# psu.net
KiCad netlist of a schematic drawn in Altium Designer
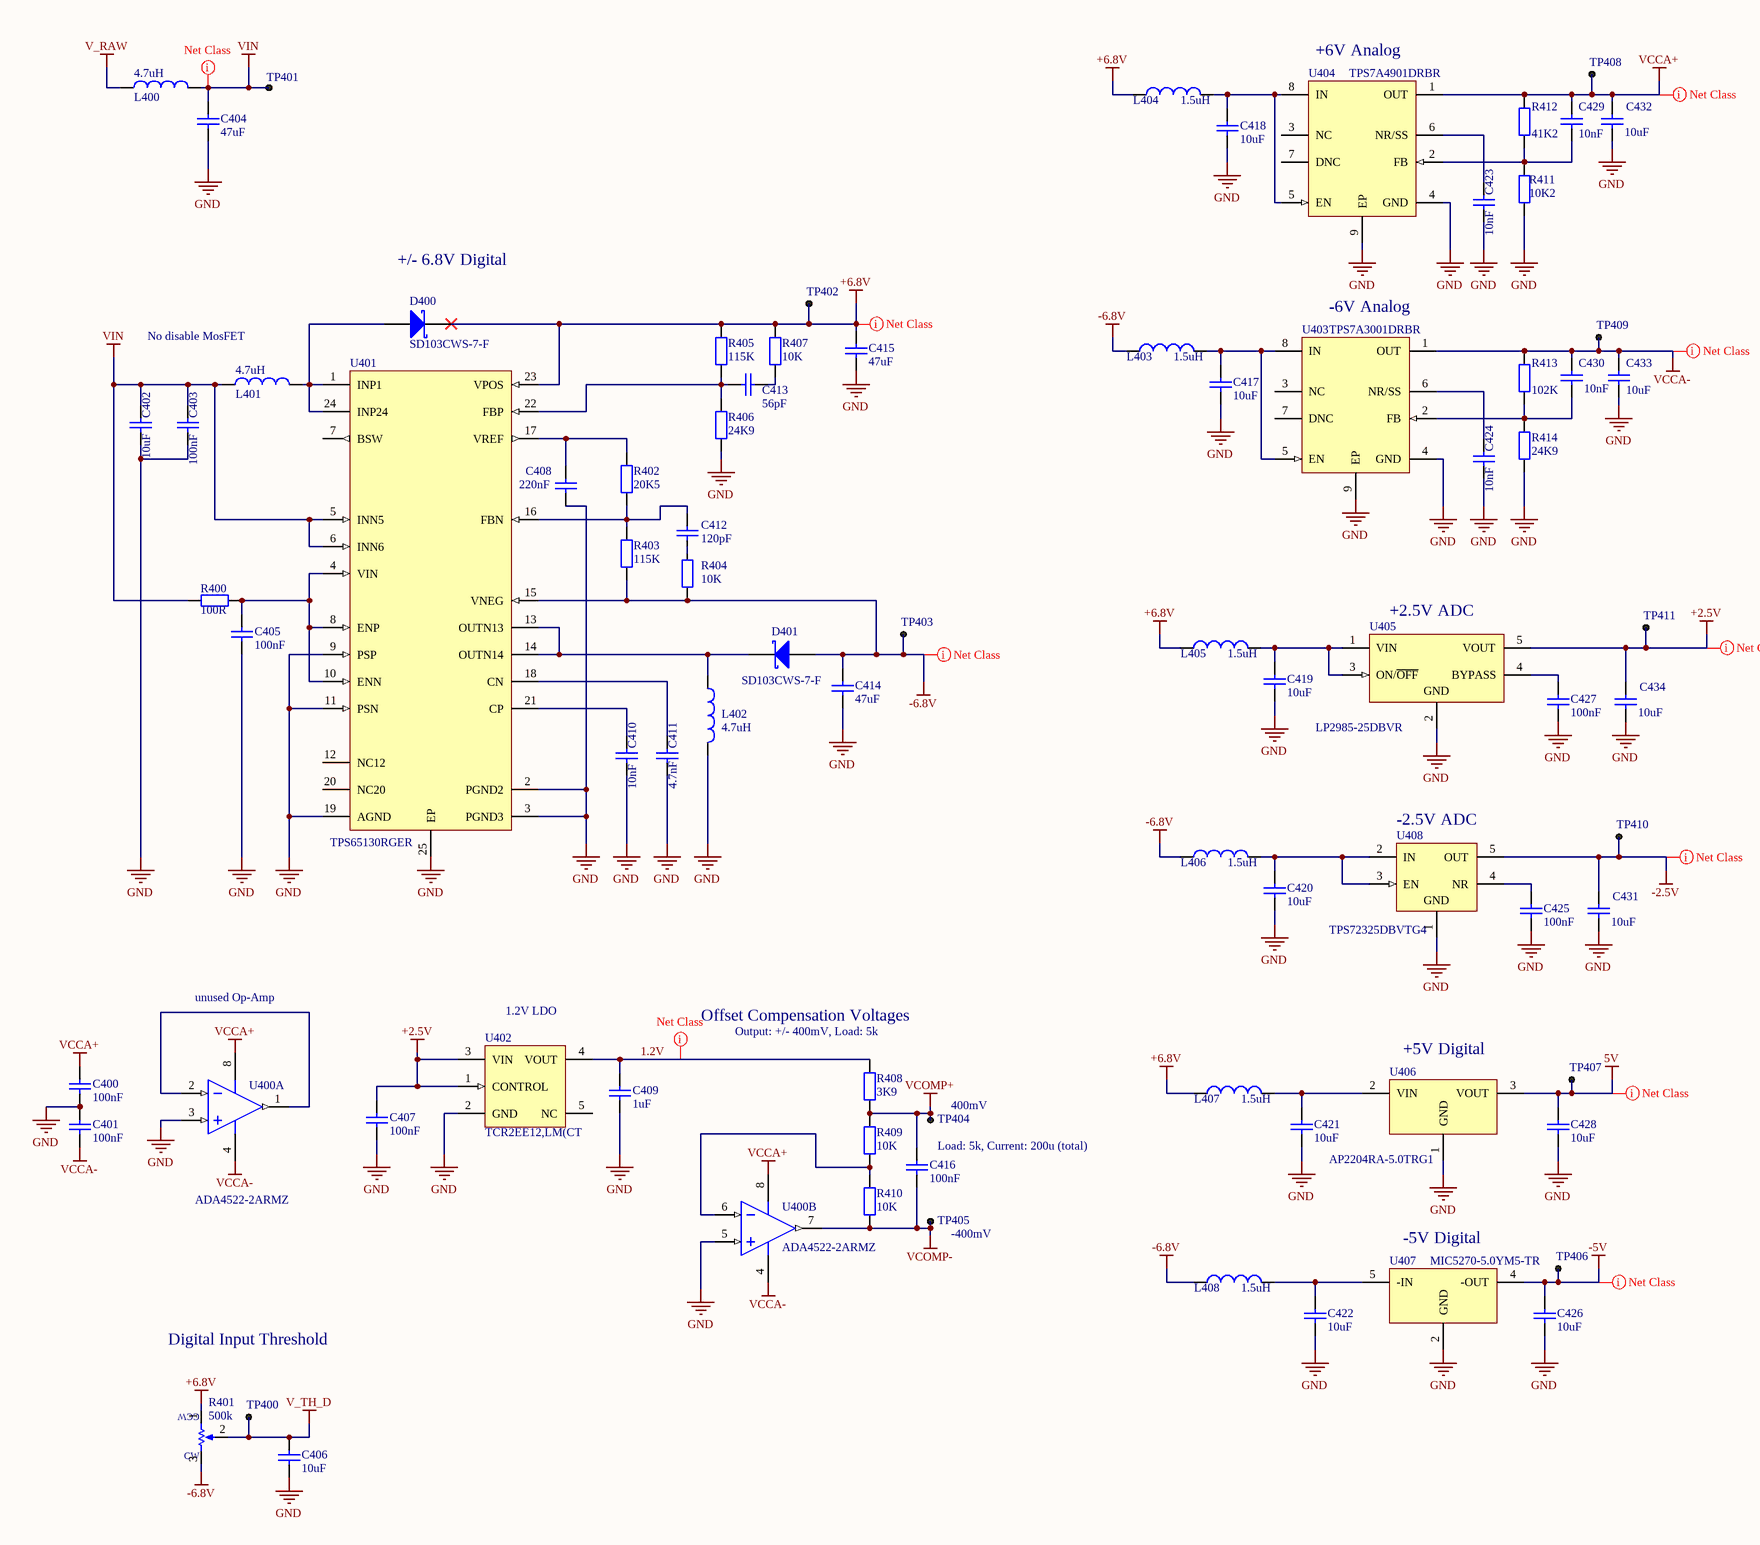
[diagram p0: psu.SchDoc]

(export (version "E")
  (design (tool "Eeschema 10.0.6"))
  (components
    (comp (ref "C400")
      (value "100nF")
      (footprint "CAPC0402(1005)60_L")
      (description "CAP 100nF 16V -20% to +80% 0402 (1005 Metric) Thickness 0.6mm SMD")
      (fields (field (name "TOLERANCE") "-20% to +80%"))
      (libsource (lib "Altium Content Vault") (part "CMP-1034-02071-1"))
    )
    (comp (ref "C401")
      (value "100nF")
      (footprint "CAPC0402(1005)60_L")
      (description "CAP 100nF 16V -20% to +80% 0402 (1005 Metric) Thickness 0.6mm SMD")
      (fields (field (name "TOLERANCE") "-20% to +80%"))
      (libsource (lib "Altium Content Vault") (part "CMP-1034-02071-1"))
    )
    (comp (ref "C402")
      (value "10uF")
      (footprint "CAPC0603(1608)100_L")
      (description "CAP 10uF 10V ±20% 0603 (1608 Metric) Thickness 1mm SMD")
      (fields (field (name "TOLERANCE") "Â±20%"))
      (libsource (lib "Altium Content Vault") (part "CMP-1035-02800-1"))
    )
    (comp (ref "C403")
      (value "100nF")
      (footprint "CAPC0402(1005)60_L")
      (description "CAP 100nF 16V -20% to +80% 0402 (1005 Metric) Thickness 0.6mm SMD")
      (fields (field (name "TOLERANCE") "-20% to +80%"))
      (libsource (lib "Altium Content Vault") (part "CMP-1034-02071-1"))
    )
    (comp (ref "C404")
      (value "47uF")
      (footprint "CAPC1210(3225)280_L")
      (description "CAP 47uF 16V ±20% 1210 (3225 Metric) Thickness 2.8mm SMD")
      (fields (field (name "TOLERANCE") "Â±20%"))
      (libsource (lib "Altium Content Vault") (part "CMP-1038-02296-1"))
    )
    (comp (ref "C405")
      (value "100nF")
      (footprint "CAPC0402(1005)60_L")
      (description "CAP 100nF 16V -20% to +80% 0402 (1005 Metric) Thickness 0.6mm SMD")
      (fields (field (name "TOLERANCE") "-20% to +80%"))
      (libsource (lib "Altium Content Vault") (part "CMP-1034-02071-1"))
    )
    (comp (ref "C406")
      (value "10uF")
      (footprint "CAPC0603(1608)100_L")
      (description "CAP 10uF 10V ±20% 0603 (1608 Metric) Thickness 1mm SMD")
      (fields (field (name "TOLERANCE") "Â±20%"))
      (libsource (lib "Altium Content Vault") (part "CMP-1035-02800-1"))
    )
    (comp (ref "C407")
      (value "100nF")
      (footprint "CAPC0402(1005)60_L")
      (description "CAP 100nF 16V -20% to +80% 0402 (1005 Metric) Thickness 0.6mm SMD")
      (fields (field (name "TOLERANCE") "-20% to +80%"))
      (libsource (lib "Altium Content Vault") (part "CMP-1034-02071-1"))
    )
    (comp (ref "C408")
      (value "220nF")
      (footprint "CAPC0402(1005)60_L")
      (description "CAP 220nF 10V -20% to +80% 0402 (1005 Metric) Thickness 0.6mm SMD")
      (fields (field (name "TOLERANCE") "-20% to +80%"))
      (libsource (lib "Altium Content Vault") (part "CMP-1034-02088-1"))
    )
    (comp (ref "C409")
      (value "1uF")
      (footprint "CAPC0402(1005)60_L")
      (description "CAP 1uF 16V ±20% 0402 (1005 Metric) Thickness 0.6mm SMD")
      (fields (field (name "TOLERANCE") "Â±20%"))
      (libsource (lib "Altium Content Vault") (part "CAP"))
    )
    (comp (ref "C410")
      (value "10nF")
      (footprint "CAPC0402(1005)60_L")
      (description "CAP 10nF 25V ±5% 0402 (1005 Metric) Thickness 0.6mm SMDC")
      (fields (field (name "TOLERANCE") "Â±5%"))
      (libsource (lib "Altium Content Vault") (part "CAP"))
    )
    (comp (ref "C411")
      (value "4.7nF")
      (footprint "CAPC0402(1005)60_L")
      (description "CAP 4.7nF 100V ±10% 0402 (1005 Metric) Thickness 0.6mm SMD")
      (fields (field (name "TOLERANCE") "Â±10%"))
      (libsource (lib "Altium Content Vault") (part "CMP-1034-01819-1"))
    )
    (comp (ref "C412")
      (value "120pF")
      (footprint "CAPC0402(1005)60_L")
      (description "CAP 120pF 100V ±1% 0402 (1005 Metric) Thickness 0.6mm SMD")
      (fields (field (name "TOLERANCE") "Â±1%"))
      (libsource (lib "Altium Content Vault") (part "CMP-1034-01278-1"))
    )
    (comp (ref "C413")
      (value "56pF")
      (footprint "CAPC0402(1005)60_L")
      (description "CAP 56pF 100V ±1% 0402 (1005 Metric) Thickness 0.6mm SMD")
      (fields (field (name "TOLERANCE") "Â±1%"))
      (libsource (lib "Altium Content Vault") (part "CMP-1034-01134-1"))
    )
    (comp (ref "C414")
      (value "47uF")
      (footprint "CAPC1210(3225)280_L")
      (description "CAP 47uF 16V ±20% 1210 (3225 Metric) Thickness 2.8mm SMD")
      (fields (field (name "TOLERANCE") "Â±20%"))
      (libsource (lib "Altium Content Vault") (part "CMP-1038-02296-1"))
    )
    (comp (ref "C415")
      (value "47uF")
      (footprint "CAPC1210(3225)280_L")
      (description "CAP 47uF 16V ±20% 1210 (3225 Metric) Thickness 2.8mm SMD")
      (fields (field (name "TOLERANCE") "Â±20%"))
      (libsource (lib "Altium Content Vault") (part "CMP-1038-02296-1"))
    )
    (comp (ref "C416")
      (value "100nF")
      (footprint "CAPC0402(1005)60_L")
      (description "CAP 100nF 16V -20% to +80% 0402 (1005 Metric) Thickness 0.6mm SMD")
      (fields (field (name "TOLERANCE") "-20% to +80%"))
      (libsource (lib "Altium Content Vault") (part "CMP-1034-02071-1"))
    )
    (comp (ref "C417")
      (value "10uF")
      (footprint "CAPC0603(1608)100_L")
      (description "CAP 10uF 10V ±20% 0603 (1608 Metric) Thickness 1mm SMD")
      (fields (field (name "TOLERANCE") "Â±20%"))
      (libsource (lib "Altium Content Vault") (part "CMP-1035-02800-1"))
    )
    (comp (ref "C418")
      (value "10uF")
      (footprint "CAPC0603(1608)100_L")
      (description "CAP 10uF 10V ±20% 0603 (1608 Metric) Thickness 1mm SMD")
      (fields (field (name "TOLERANCE") "Â±20%"))
      (libsource (lib "Altium Content Vault") (part "CMP-1035-02800-1"))
    )
    (comp (ref "C419")
      (value "10uF")
      (footprint "CAPC0603(1608)100_L")
      (description "CAP 10uF 10V ±20% 0603 (1608 Metric) Thickness 1mm SMD")
      (fields (field (name "TOLERANCE") "Â±20%"))
      (libsource (lib "Altium Content Vault") (part "CMP-1035-02800-1"))
    )
    (comp (ref "C420")
      (value "10uF")
      (footprint "CAPC0603(1608)100_L")
      (description "CAP 10uF 10V ±20% 0603 (1608 Metric) Thickness 1mm SMD")
      (fields (field (name "TOLERANCE") "Â±20%"))
      (libsource (lib "Altium Content Vault") (part "CMP-1035-02800-1"))
    )
    (comp (ref "C421")
      (value "10uF")
      (footprint "CAPC0603(1608)100_L")
      (description "CAP 10uF 10V ±20% 0603 (1608 Metric) Thickness 1mm SMD")
      (fields (field (name "TOLERANCE") "Â±20%"))
      (libsource (lib "Altium Content Vault") (part "CMP-1035-02800-1"))
    )
    (comp (ref "C422")
      (value "10uF")
      (footprint "CAPC0603(1608)100_L")
      (description "CAP 10uF 10V ±20% 0603 (1608 Metric) Thickness 1mm SMD")
      (fields (field (name "TOLERANCE") "Â±20%"))
      (libsource (lib "Altium Content Vault") (part "CMP-1035-02800-1"))
    )
    (comp (ref "C423")
      (value "10nF")
      (footprint "CAPC0402(1005)60_L")
      (description "CAP 10nF 25V ±5% 0402 (1005 Metric) Thickness 0.6mm SMDC")
      (fields (field (name "TOLERANCE") "Â±5%"))
      (libsource (lib "Altium Content Vault") (part "CAP"))
    )
    (comp (ref "C424")
      (value "10nF")
      (footprint "CAPC0402(1005)60_L")
      (description "CAP 10nF 25V ±5% 0402 (1005 Metric) Thickness 0.6mm SMDC")
      (fields (field (name "TOLERANCE") "Â±5%"))
      (libsource (lib "Altium Content Vault") (part "CAP"))
    )
    (comp (ref "C425")
      (value "100nF")
      (footprint "CAPC0402(1005)60_L")
      (description "CAP 100nF 16V -20% to +80% 0402 (1005 Metric) Thickness 0.6mm SMD")
      (fields (field (name "TOLERANCE") "-20% to +80%"))
      (libsource (lib "Altium Content Vault") (part "CMP-1034-02071-1"))
    )
    (comp (ref "C426")
      (value "10uF")
      (footprint "CAPC0603(1608)100_L")
      (description "CAP 10uF 10V ±20% 0603 (1608 Metric) Thickness 1mm SMD")
      (fields (field (name "TOLERANCE") "Â±20%"))
      (libsource (lib "Altium Content Vault") (part "CMP-1035-02800-1"))
    )
    (comp (ref "C427")
      (value "100nF")
      (footprint "CAPC0402(1005)60_L")
      (description "CAP 100nF 16V -20% to +80% 0402 (1005 Metric) Thickness 0.6mm SMD")
      (fields (field (name "TOLERANCE") "-20% to +80%"))
      (libsource (lib "Altium Content Vault") (part "CMP-1034-02071-1"))
    )
    (comp (ref "C428")
      (value "10uF")
      (footprint "CAPC0603(1608)100_L")
      (description "CAP 10uF 10V ±20% 0603 (1608 Metric) Thickness 1mm SMD")
      (fields (field (name "TOLERANCE") "Â±20%"))
      (libsource (lib "Altium Content Vault") (part "CMP-1035-02800-1"))
    )
    (comp (ref "C429")
      (value "10nF")
      (footprint "CAPC0402(1005)60_L")
      (description "CAP 10nF 25V ±5% 0402 (1005 Metric) Thickness 0.6mm SMDC")
      (fields (field (name "TOLERANCE") "Â±5%"))
      (libsource (lib "Altium Content Vault") (part "CAP"))
    )
    (comp (ref "C430")
      (value "10nF")
      (footprint "CAPC0402(1005)60_L")
      (description "CAP 10nF 25V ±5% 0402 (1005 Metric) Thickness 0.6mm SMDC")
      (fields (field (name "TOLERANCE") "Â±5%"))
      (libsource (lib "Altium Content Vault") (part "CAP"))
    )
    (comp (ref "C431")
      (value "10uF")
      (footprint "CAPC0603(1608)100_L")
      (description "CAP 10uF 10V ±20% 0603 (1608 Metric) Thickness 1mm SMD")
      (fields (field (name "TOLERANCE") "Â±20%"))
      (libsource (lib "Altium Content Vault") (part "CMP-1035-02800-1"))
    )
    (comp (ref "C432")
      (value "10uF")
      (footprint "CAPC0603(1608)100_L")
      (description "CAP 10uF 10V ±20% 0603 (1608 Metric) Thickness 1mm SMD")
      (fields (field (name "TOLERANCE") "Â±20%"))
      (libsource (lib "Altium Content Vault") (part "CMP-1035-02800-1"))
    )
    (comp (ref "C433")
      (value "10uF")
      (footprint "CAPC0603(1608)100_L")
      (description "CAP 10uF 10V ±20% 0603 (1608 Metric) Thickness 1mm SMD")
      (fields (field (name "TOLERANCE") "Â±20%"))
      (libsource (lib "Altium Content Vault") (part "CMP-1035-02800-1"))
    )
    (comp (ref "C434")
      (value "10uF")
      (footprint "CAPC0603(1608)100_L")
      (description "CAP 10uF 10V ±20% 0603 (1608 Metric) Thickness 1mm SMD")
      (fields (field (name "TOLERANCE") "Â±20%"))
      (libsource (lib "Altium Content Vault") (part "CMP-1035-02800-1"))
    )
    (comp (ref "D400")
      (value "SD103CWS-7-F")
      (footprint "DIOD-SOD323-2_V")
      (description "DIODE SCHOTTKY 20V 350MA SOD323")
      (fields (field (name "MANUFACTURER") "Diodes Incorporated"))
      (libsource (lib "ETHZ Vault") (part "Diode Schottky"))
    )
    (comp (ref "D401")
      (value "SD103CWS-7-F")
      (footprint "DIOD-SOD323-2_V")
      (description "DIODE SCHOTTKY 20V 350MA SOD323")
      (fields (field (name "MANUFACTURER") "Diodes Incorporated"))
      (libsource (lib "ETHZ Vault") (part "Diode Schottky"))
    )
    (comp (ref "L400")
      (value "4.7uH")
      (footprint "INDC2520X10L")
      (description "FIXED IND 4.7UH 1A 110 MOHM SMD")
      (fields (field (name "TOLERANCE") "±20%") (field (name "MANUFACTURER") "TDK Corporation"))
      (libsource (lib "ETHZ Vault") (part "CMP-00119-1"))
    )
    (comp (ref "L401")
      (value "4.7uH")
      (footprint "INDC2520X10L")
      (description "FIXED IND 4.7UH 1A 110 MOHM SMD")
      (fields (field (name "TOLERANCE") "±20%") (field (name "MANUFACTURER") "TDK Corporation"))
      (libsource (lib "ETHZ Vault") (part "CMP-00119-1"))
    )
    (comp (ref "L402")
      (value "4.7uH")
      (footprint "INDC2520X10L")
      (description "FIXED IND 4.7UH 1A 110 MOHM SMD")
      (fields (field (name "TOLERANCE") "±20%") (field (name "MANUFACTURER") "TDK Corporation"))
      (libsource (lib "ETHZ Vault") (part "CMP-00119-1"))
    )
    (comp (ref "L403")
      (value "1.5uH")
      (footprint "INDC0603(1608)_L")
      (description "FIXED IND 1.5UH 50MA 700 MOHM")
      (fields (field (name "TOLERANCE") "±20%") (field (name "MANUFACTURER") "TDK Corporation"))
      (libsource (lib "ETHZ Vault") (part "CMP-00229-1"))
    )
    (comp (ref "L404")
      (value "1.5uH")
      (footprint "INDC0603(1608)_L")
      (description "FIXED IND 1.5UH 50MA 700 MOHM")
      (fields (field (name "TOLERANCE") "±20%") (field (name "MANUFACTURER") "TDK Corporation"))
      (libsource (lib "ETHZ Vault") (part "CMP-00229-1"))
    )
    (comp (ref "L405")
      (value "1.5uH")
      (footprint "INDC0603(1608)_L")
      (description "FIXED IND 1.5UH 50MA 700 MOHM")
      (fields (field (name "TOLERANCE") "±20%") (field (name "MANUFACTURER") "TDK Corporation"))
      (libsource (lib "ETHZ Vault") (part "CMP-00229-1"))
    )
    (comp (ref "L406")
      (value "1.5uH")
      (footprint "INDC0603(1608)_L")
      (description "FIXED IND 1.5UH 50MA 700 MOHM")
      (fields (field (name "TOLERANCE") "±20%") (field (name "MANUFACTURER") "TDK Corporation"))
      (libsource (lib "ETHZ Vault") (part "CMP-00229-1"))
    )
    (comp (ref "L407")
      (value "1.5uH")
      (footprint "INDC0603(1608)_L")
      (description "FIXED IND 1.5UH 50MA 700 MOHM")
      (fields (field (name "TOLERANCE") "±20%") (field (name "MANUFACTURER") "TDK Corporation"))
      (libsource (lib "ETHZ Vault") (part "CMP-00229-1"))
    )
    (comp (ref "L408")
      (value "1.5uH")
      (footprint "INDC0603(1608)_L")
      (description "FIXED IND 1.5UH 50MA 700 MOHM")
      (fields (field (name "TOLERANCE") "±20%") (field (name "MANUFACTURER") "TDK Corporation"))
      (libsource (lib "ETHZ Vault") (part "CMP-00229-1"))
    )
    (comp (ref "R400")
      (value "100R")
      (footprint "RESC0402(1005)_L")
      (description "100R 0.063W 1% 0402 (1005 Metric)  SMD")
      (fields (field (name "TOLERANCE") "1 %") (field (name "POWER") "0.063 W"))
      (libsource (lib "Altium Content Vault") (part "CMP-1011-00397-1"))
    )
    (comp (ref "R401")
      (value "500k")
      (footprint "43W")
      (description "TRIMMER 500K OHM 0.125W SMD")
      (fields (field (name "TOLERANCE") "±20%") (field (name "MANUFACTURER") "TT Electronics/BI"))
      (libsource (lib "ETHZ Vault") (part "Trimmer"))
    )
    (comp (ref "R402")
      (value "20K5")
      (footprint "RESC0402(1005)_L")
      (description "20K5 0.063W 1% 0402 (1005 Metric)  SMD")
      (fields (field (name "POWER") "0.063 W") (field (name "TOLERANCE") "1 %"))
      (libsource (lib "Altium Content Vault") (part "RES"))
    )
    (comp (ref "R403")
      (value "115K")
      (footprint "RESC0402(1005)_L")
      (description "115K 0.063W 1% 0402 (1005 Metric)  SMD")
      (fields (field (name "TOLERANCE") "1 %") (field (name "POWER") "0.063 W"))
      (libsource (lib "") (part "RES_1"))
    )
    (comp (ref "R404")
      (value "10K")
      (footprint "RESC0402(1005)_L")
      (description "10K 0.063W 1% 0402 (1005 Metric)  SMD")
      (fields (field (name "TOLERANCE") "1 %") (field (name "POWER") "0.063 W"))
      (libsource (lib "Altium Content Vault") (part "CMP-1011-00623-1"))
    )
    (comp (ref "R405")
      (value "115K")
      (footprint "RESC0402(1005)_L")
      (description "115K 0.063W 1% 0402 (1005 Metric)  SMD")
      (fields (field (name "TOLERANCE") "1 %") (field (name "POWER") "0.063 W"))
      (libsource (lib "Altium Content Vault") (part "RES"))
    )
    (comp (ref "R406")
      (value "24K9")
      (footprint "RESC0402(1005)_L")
      (description "24K9 0.063W 1% 0402 (1005 Metric)  SMD")
      (fields (field (name "TOLERANCE") "1 %") (field (name "POWER") "0.063 W"))
      (libsource (lib "Altium Content Vault") (part "RES"))
    )
    (comp (ref "R407")
      (value "10K")
      (footprint "RESC0402(1005)_L")
      (description "10K 0.063W 1% 0402 (1005 Metric)  SMD")
      (fields (field (name "TOLERANCE") "1 %") (field (name "POWER") "0.063 W"))
      (libsource (lib "Altium Content Vault") (part "CMP-1011-00623-1"))
    )
    (comp (ref "R408")
      (value "3K9")
      (footprint "RESC0402(1005)_L")
      (description "3K9 0.063W 1% 0402 (1005 Metric)  SMD")
      (fields (field (name "TOLERANCE") "1 %") (field (name "POWER") "0.063 W"))
      (libsource (lib "Altium Content Vault") (part "RES"))
    )
    (comp (ref "R409")
      (value "10K")
      (footprint "RESC0402(1005)_L")
      (description "10K 0.063W 1% 0402 (1005 Metric)  SMD")
      (fields (field (name "TOLERANCE") "1 %") (field (name "POWER") "0.063 W"))
      (libsource (lib "Altium Content Vault") (part "RES"))
    )
    (comp (ref "R410")
      (value "10K")
      (footprint "RESC0402(1005)_L")
      (description "10K 0.063W 1% 0402 (1005 Metric)  SMD")
      (fields (field (name "TOLERANCE") "1 %") (field (name "POWER") "0.063 W"))
      (libsource (lib "Altium Content Vault") (part "RES"))
    )
    (comp (ref "R411")
      (value "10K2")
      (footprint "RESC0402(1005)_L")
      (description "10K2 0.063W 1% 0402 (1005 Metric)  SMD")
      (fields (field (name "POWER") "0.063 W") (field (name "TOLERANCE") "1 %"))
      (libsource (lib "Altium Content Vault") (part "CMP-1011-00624-1"))
    )
    (comp (ref "R412")
      (value "41K2")
      (footprint "RESC0402(1005)_L")
      (description "41K2 0.063W 1% 0402 (1005 Metric)  SMD")
      (fields (field (name "TOLERANCE") "1 %") (field (name "POWER") "0.063 W"))
      (libsource (lib "Altium Content Vault") (part "CMP-1011-00692-1"))
    )
    (comp (ref "R413")
      (value "102K")
      (footprint "RESC0402(1005)_L")
      (description "102K 0.063W 1% 0402 (1005 Metric)  SMD")
      (fields (field (name "TOLERANCE") "1 %") (field (name "POWER") "0.063 W"))
      (libsource (lib "Altium Content Vault") (part "CMP-1011-00737-1"))
    )
    (comp (ref "R414")
      (value "24K9")
      (footprint "RESC0402(1005)_L")
      (description "24K9 0.063W 1% 0402 (1005 Metric)  SMD")
      (fields (field (name "TOLERANCE") "1 %") (field (name "POWER") "0.063 W"))
      (libsource (lib "Altium Content Vault") (part "CMP-1011-00666-1"))
    )
    (comp (ref "TP400")
      (value "~")
      (footprint "Pad-0.6mm")
      (description "0.6mm SMT Test Pad")
      (libsource (lib "ETHZ Vault") (part "Test Pad"))
    )
    (comp (ref "TP401")
      (value "~")
      (footprint "Pad-0.6mm")
      (description "0.6mm SMT Test Pad")
      (libsource (lib "ETHZ Vault") (part "Test Pad"))
    )
    (comp (ref "TP402")
      (value "~")
      (footprint "Pad-0.6mm")
      (description "0.6mm SMT Test Pad")
      (libsource (lib "ETHZ Vault") (part "Test Pad"))
    )
    (comp (ref "TP403")
      (value "~")
      (footprint "Pad-0.6mm")
      (description "0.6mm SMT Test Pad")
      (libsource (lib "ETHZ Vault") (part "Test Pad"))
    )
    (comp (ref "TP404")
      (value "~")
      (footprint "Pad-0.6mm")
      (description "0.6mm SMT Test Pad")
      (libsource (lib "ETHZ Vault") (part "Test Pad"))
    )
    (comp (ref "TP405")
      (value "~")
      (footprint "Pad-0.6mm")
      (description "0.6mm SMT Test Pad")
      (libsource (lib "ETHZ Vault") (part "Test Pad"))
    )
    (comp (ref "TP406")
      (value "~")
      (footprint "Pad-0.6mm")
      (description "0.6mm SMT Test Pad")
      (libsource (lib "ETHZ Vault") (part "Test Pad"))
    )
    (comp (ref "TP407")
      (value "~")
      (footprint "Pad-0.6mm")
      (description "0.6mm SMT Test Pad")
      (libsource (lib "ETHZ Vault") (part "Test Pad"))
    )
    (comp (ref "TP408")
      (value "~")
      (footprint "Pad-0.6mm")
      (description "0.6mm SMT Test Pad")
      (libsource (lib "ETHZ Vault") (part "Test Pad"))
    )
    (comp (ref "TP409")
      (value "~")
      (footprint "Pad-0.6mm")
      (description "0.6mm SMT Test Pad")
      (libsource (lib "ETHZ Vault") (part "Test Pad"))
    )
    (comp (ref "TP410")
      (value "~")
      (footprint "Pad-0.6mm")
      (description "0.6mm SMT Test Pad")
      (libsource (lib "ETHZ Vault") (part "Test Pad"))
    )
    (comp (ref "TP411")
      (value "~")
      (footprint "Pad-0.6mm")
      (description "0.6mm SMT Test Pad")
      (libsource (lib "ETHZ Vault") (part "Test Pad"))
    )
    (comp (ref "U400")
      (value "ADA4522-2ARMZ")
      (footprint "ADI-RM-8_L")
      (description "SP Amp Zero Drift Amplifier Dual R-R I/O ±27.5V/55V 8-Pin MSOP")
      (fields (field (name "MANUFACTURER") "Analog Devices Inc."))
      (libsource (lib "ETHZ Vault") (part "TLV1702"))
    )
    (comp (ref "U401")
      (value "TPS65130RGER")
      (footprint "LT-UF-24_L")
      (description "Conv DC-DC Dual Inv/Step Up 2.7V to 5.5V 24-Pin VQFN EP")
      (fields (field (name "MANUFACTURER") "Texas Instruments"))
      (libsource (lib "ETHZ Vault") (part "TPS65130"))
    )
    (comp (ref "U402")
      (value "TCR2EE12,LM(CT")
      (footprint "TI-DRL5_L")
      (description "IC REG LDO 1.2V 0.2A ESV")
      (fields (field (name "MANUFACTURER") "Toshiba Semiconductor and Storage"))
      (libsource (lib "ETHZ Vault") (part "TCR2EE12,LM(CT"))
    )
    (comp (ref "U403")
      (value "TPS7A3001DRBR")
      (footprint "DRB8-1750X1500TP")
      (fields (field (name "MANUFACTURER") "Texas Instruments"))
      (libsource (lib "ETHZ Vault") (part "TPS7A30"))
    )
    (comp (ref "U404")
      (value "TPS7A4901DRBR")
      (footprint "DRB8-1750X1500TP")
      (fields (field (name "MANUFACTURER") "Texas Instruments"))
      (libsource (lib "ETHZ Vault") (part "TPS7A30"))
    )
    (comp (ref "U405")
      (value "LP2985-25DBVR")
      (footprint "DBV0005A_L")
      (fields (field (name "MANUFACTURER") "Texas Instruments"))
      (libsource (lib "Altium Content Vault") (part "TI-LP2985_A-10DBV5"))
    )
    (comp (ref "U406")
      (value "AP2204RA-5.0TRG1")
      (footprint "SOT89_L")
      (description "IC REG LDO Linear Voltage Regulator Positive Fixed 1 Output 5V 150mA SOT-89-3")
      (fields (field (name "MANUFACTURER") "Diodes Incorporated"))
      (libsource (lib "ETHZ Vault") (part "AP2204RA"))
    )
    (comp (ref "U407")
      (value "MIC5270-5.0YM5-TR")
      (footprint "Z5+1_L")
      (description "IC REG LDO Linear Voltage Regulator Negative Fixed 1 Output -5V 100mA SOT-23-5")
      (fields (field (name "MANUFACTURER") "Microchip Technology"))
      (libsource (lib "ETHZ Vault") (part "MIC5270"))
    )
    (comp (ref "U408")
      (value "TPS72325DBVTG4")
      (footprint "TI-DBV5_L")
      (fields (field (name "MANUFACTURER") "Texas Instruments"))
      (libsource (lib "Altium Content Vault") (part "CMP-0394-00283-1"))
    )
  )
  (nets
    (net (code "1") (name "+2.5V") (class "Default")
      (node (ref "C407") (pin "2") (pinfunction "2_2") (pintype "passive"))
      (node (ref "C434") (pin "2") (pinfunction "2_2") (pintype "passive"))
      (node (ref "TP411") (pin "1") (pinfunction "1_1") (pintype "passive"))
      (node (ref "U402") (pin "1") (pinfunction "CONTROL_1") (pintype "input"))
      (node (ref "U402") (pin "3") (pinfunction "VIN_3") (pintype "power_in"))
      (node (ref "U405") (pin "5") (pinfunction "VOUT_5") (pintype "power_in"))
    )
    (net (code "2") (name "+6.8V") (class "Default")
      (node (ref "C415") (pin "1") (pinfunction "1_1") (pintype "passive"))
      (node (ref "D400") (pin "2") (pinfunction "K_2") (pintype "passive"))
      (node (ref "L404") (pin "1") (pinfunction "1_1") (pintype "passive"))
      (node (ref "L405") (pin "1") (pinfunction "1_1") (pintype "passive"))
      (node (ref "L407") (pin "1") (pinfunction "1_1") (pintype "passive"))
      (node (ref "R401") (pin "1") (pinfunction "CCW_1") (pintype "passive"))
      (node (ref "R405") (pin "2") (pinfunction "2_2") (pintype "passive"))
      (node (ref "R407") (pin "2") (pinfunction "2_2") (pintype "passive"))
      (node (ref "TP402") (pin "1") (pinfunction "1_1") (pintype "passive"))
      (node (ref "U401") (pin "23") (pinfunction "VPOS_23") (pintype "input"))
    )
    (net (code "3") (name "-2.5V") (class "Default")
      (node (ref "C431") (pin "2") (pinfunction "2_2") (pintype "passive"))
      (node (ref "TP410") (pin "1") (pinfunction "1_1") (pintype "passive"))
      (node (ref "U408") (pin "5") (pinfunction "OUT_5") (pintype "power_in"))
    )
    (net (code "4") (name "-5V") (class "Default")
      (node (ref "C426") (pin "2") (pinfunction "2_2") (pintype "passive"))
      (node (ref "TP406") (pin "1") (pinfunction "1_1") (pintype "passive"))
      (node (ref "U407") (pin "4") (pinfunction "-OUT_4") (pintype "power_in"))
    )
    (net (code "5") (name "-6.8V") (class "Default")
      (node (ref "C414") (pin "1") (pinfunction "1_1") (pintype "passive"))
      (node (ref "D401") (pin "1") (pinfunction "A_1") (pintype "passive"))
      (node (ref "L403") (pin "1") (pinfunction "1_1") (pintype "passive"))
      (node (ref "L406") (pin "1") (pinfunction "1_1") (pintype "passive"))
      (node (ref "L408") (pin "1") (pinfunction "1_1") (pintype "passive"))
      (node (ref "R401") (pin "3") (pinfunction "CW_3") (pintype "passive"))
      (node (ref "R403") (pin "2") (pinfunction "2_2") (pintype "passive"))
      (node (ref "R404") (pin "1") (pinfunction "1_1") (pintype "passive"))
      (node (ref "TP403") (pin "1") (pinfunction "1_1") (pintype "passive"))
      (node (ref "U401") (pin "15") (pinfunction "VNEG_15") (pintype "input"))
    )
    (net (code "6") (name "/1.2V") (class "Default")
      (node (ref "C409") (pin "2") (pinfunction "2_2") (pintype "passive"))
      (node (ref "R408") (pin "2") (pinfunction "2_2") (pintype "passive"))
      (node (ref "U402") (pin "4") (pinfunction "VOUT_4") (pintype "power_in"))
    )
    (net (code "7") (name "5V") (class "Default")
      (node (ref "C428") (pin "2") (pinfunction "2_2") (pintype "passive"))
      (node (ref "TP407") (pin "1") (pinfunction "1_1") (pintype "passive"))
      (node (ref "U406") (pin "3") (pinfunction "VOUT_3") (pintype "power_in"))
    )
    (net (code "8") (name "GND") (class "Default")
      (node (ref "C400") (pin "1") (pinfunction "1_1") (pintype "passive"))
      (node (ref "C401") (pin "2") (pinfunction "2_2") (pintype "passive"))
      (node (ref "C402") (pin "1") (pinfunction "1_1") (pintype "passive"))
      (node (ref "C403") (pin "1") (pinfunction "1_1") (pintype "passive"))
      (node (ref "C404") (pin "2") (pinfunction "2_2") (pintype "passive"))
      (node (ref "C405") (pin "1") (pinfunction "1_1") (pintype "passive"))
      (node (ref "C406") (pin "1") (pinfunction "1_1") (pintype "passive"))
      (node (ref "C407") (pin "1") (pinfunction "1_1") (pintype "passive"))
      (node (ref "C408") (pin "1") (pinfunction "1_1") (pintype "passive"))
      (node (ref "C409") (pin "1") (pinfunction "1_1") (pintype "passive"))
      (node (ref "C410") (pin "1") (pinfunction "1_1") (pintype "passive"))
      (node (ref "C411") (pin "1") (pinfunction "1_1") (pintype "passive"))
      (node (ref "C414") (pin "2") (pinfunction "2_2") (pintype "passive"))
      (node (ref "C415") (pin "2") (pinfunction "2_2") (pintype "passive"))
      (node (ref "C417") (pin "1") (pinfunction "1_1") (pintype "passive"))
      (node (ref "C418") (pin "1") (pinfunction "1_1") (pintype "passive"))
      (node (ref "C419") (pin "1") (pinfunction "1_1") (pintype "passive"))
      (node (ref "C420") (pin "1") (pinfunction "1_1") (pintype "passive"))
      (node (ref "C421") (pin "1") (pinfunction "1_1") (pintype "passive"))
      (node (ref "C422") (pin "1") (pinfunction "1_1") (pintype "passive"))
      (node (ref "C423") (pin "1") (pinfunction "1_1") (pintype "passive"))
      (node (ref "C424") (pin "1") (pinfunction "1_1") (pintype "passive"))
      (node (ref "C425") (pin "1") (pinfunction "1_1") (pintype "passive"))
      (node (ref "C426") (pin "1") (pinfunction "1_1") (pintype "passive"))
      (node (ref "C427") (pin "1") (pinfunction "1_1") (pintype "passive"))
      (node (ref "C428") (pin "1") (pinfunction "1_1") (pintype "passive"))
      (node (ref "C431") (pin "1") (pinfunction "1_1") (pintype "passive"))
      (node (ref "C432") (pin "1") (pinfunction "1_1") (pintype "passive"))
      (node (ref "C433") (pin "1") (pinfunction "1_1") (pintype "passive"))
      (node (ref "C434") (pin "1") (pinfunction "1_1") (pintype "passive"))
      (node (ref "L402") (pin "2") (pinfunction "2_2") (pintype "passive"))
      (node (ref "R406") (pin "1") (pinfunction "1_1") (pintype "passive"))
      (node (ref "R411") (pin "1") (pinfunction "1_1") (pintype "passive"))
      (node (ref "R414") (pin "1") (pinfunction "1_1") (pintype "passive"))
      (node (ref "U400") (pin "3") (pinfunction "1IN+_3") (pintype "input"))
      (node (ref "U400") (pin "5") (pinfunction "2IN+_5") (pintype "input"))
      (node (ref "U401") (pin "11") (pinfunction "PSN_11") (pintype "input"))
      (node (ref "U401") (pin "19") (pinfunction "AGND_19") (pintype "power_in"))
      (node (ref "U401") (pin "2") (pinfunction "PGND2_2") (pintype "power_in"))
      (node (ref "U401") (pin "25") (pinfunction "EP_25") (pintype "passive"))
      (node (ref "U401") (pin "3") (pinfunction "PGND3_3") (pintype "power_in"))
      (node (ref "U401") (pin "9") (pinfunction "PSP_9") (pintype "input"))
      (node (ref "U402") (pin "2") (pinfunction "GND_2") (pintype "power_in"))
      (node (ref "U403") (pin "4") (pinfunction "GND_4") (pintype "power_in"))
      (node (ref "U403") (pin "9") (pinfunction "EP_9") (pintype "power_in"))
      (node (ref "U404") (pin "4") (pinfunction "GND_4") (pintype "power_in"))
      (node (ref "U404") (pin "9") (pinfunction "EP_9") (pintype "power_in"))
      (node (ref "U405") (pin "2") (pinfunction "GND_2") (pintype "power_in"))
      (node (ref "U406") (pin "1") (pinfunction "GND_1") (pintype "power_in"))
      (node (ref "U407") (pin "2") (pinfunction "GND_2") (pintype "power_in"))
      (node (ref "U408") (pin "1") (pinfunction "GND_1") (pintype "power_in"))
    )
    (net (code "9") (name "Net-(C412-Pad1)") (class "Default")
      (node (ref "C412") (pin "1") (pinfunction "1_1") (pintype "passive"))
      (node (ref "R404") (pin "2") (pinfunction "2_2") (pintype "passive"))
    )
    (net (code "10") (name "Net-(C413-Pad1)") (class "Default")
      (node (ref "C413") (pin "1") (pinfunction "1_1") (pintype "passive"))
      (node (ref "R407") (pin "1") (pinfunction "1_1") (pintype "passive"))
    )
    (net (code "11") (name "Net-(D400-A)") (class "Default")
      (node (ref "D400") (pin "1") (pinfunction "A_1") (pintype "passive"))
      (node (ref "L401") (pin "2") (pinfunction "2_2") (pintype "passive"))
      (node (ref "U401") (pin "1") (pinfunction "INP1_1") (pintype "power_in"))
      (node (ref "U401") (pin "24") (pinfunction "INP24_24") (pintype "power_in"))
    )
    (net (code "12") (name "Net-(D401-K)") (class "Default")
      (node (ref "D401") (pin "2") (pinfunction "K_2") (pintype "passive"))
      (node (ref "L402") (pin "1") (pinfunction "1_1") (pintype "passive"))
      (node (ref "U401") (pin "13") (pinfunction "OUTN13_13") (pintype "power_in"))
      (node (ref "U401") (pin "14") (pinfunction "OUTN14_14") (pintype "power_in"))
    )
    (net (code "13") (name "Net-(U400A-1IN-)") (class "Default")
      (node (ref "U400") (pin "1") (pinfunction "1OUT_1") (pintype "output"))
      (node (ref "U400") (pin "2") (pinfunction "1IN-_2") (pintype "input"))
    )
    (net (code "14") (name "Net-(U400B-2IN-)") (class "Default")
      (node (ref "R409") (pin "1") (pinfunction "1_1") (pintype "passive"))
      (node (ref "R410") (pin "2") (pinfunction "2_2") (pintype "passive"))
      (node (ref "U400") (pin "6") (pinfunction "2IN-_6") (pintype "input"))
    )
    (net (code "15") (name "Net-(U401-CN)") (class "Default")
      (node (ref "C411") (pin "2") (pinfunction "2_2") (pintype "passive"))
      (node (ref "U401") (pin "18") (pinfunction "CN_18") (pintype "passive"))
    )
    (net (code "16") (name "Net-(U401-CP)") (class "Default")
      (node (ref "C410") (pin "2") (pinfunction "2_2") (pintype "passive"))
      (node (ref "U401") (pin "21") (pinfunction "CP_21") (pintype "passive"))
    )
    (net (code "17") (name "Net-(U401-ENN)") (class "Default")
      (node (ref "C405") (pin "2") (pinfunction "2_2") (pintype "passive"))
      (node (ref "R400") (pin "1") (pinfunction "1_1") (pintype "passive"))
      (node (ref "U401") (pin "10") (pinfunction "ENN_10") (pintype "input"))
      (node (ref "U401") (pin "4") (pinfunction "VIN_4") (pintype "input"))
      (node (ref "U401") (pin "8") (pinfunction "ENP_8") (pintype "input"))
    )
    (net (code "18") (name "Net-(U401-FBN)") (class "Default")
      (node (ref "C412") (pin "2") (pinfunction "2_2") (pintype "passive"))
      (node (ref "R402") (pin "1") (pinfunction "1_1") (pintype "passive"))
      (node (ref "R403") (pin "1") (pinfunction "1_1") (pintype "passive"))
      (node (ref "U401") (pin "16") (pinfunction "FBN_16") (pintype "input"))
    )
    (net (code "19") (name "Net-(U401-FBP)") (class "Default")
      (node (ref "C413") (pin "2") (pinfunction "2_2") (pintype "passive"))
      (node (ref "R405") (pin "1") (pinfunction "1_1") (pintype "passive"))
      (node (ref "R406") (pin "2") (pinfunction "2_2") (pintype "passive"))
      (node (ref "U401") (pin "22") (pinfunction "FBP_22") (pintype "input"))
    )
    (net (code "20") (name "Net-(U401-VREF)") (class "Default")
      (node (ref "C408") (pin "2") (pinfunction "2_2") (pintype "passive"))
      (node (ref "R402") (pin "2") (pinfunction "2_2") (pintype "passive"))
      (node (ref "U401") (pin "17") (pinfunction "VREF_17") (pintype "output"))
    )
    (net (code "21") (name "Net-(U403-EN)") (class "Default")
      (node (ref "C417") (pin "2") (pinfunction "2_2") (pintype "passive"))
      (node (ref "L403") (pin "2") (pinfunction "2_2") (pintype "passive"))
      (node (ref "U403") (pin "5") (pinfunction "EN_5") (pintype "input"))
      (node (ref "U403") (pin "8") (pinfunction "IN_8") (pintype "power_in"))
    )
    (net (code "22") (name "Net-(U403-FB)") (class "Default")
      (node (ref "C430") (pin "1") (pinfunction "1_1") (pintype "passive"))
      (node (ref "R413") (pin "1") (pinfunction "1_1") (pintype "passive"))
      (node (ref "R414") (pin "2") (pinfunction "2_2") (pintype "passive"))
      (node (ref "U403") (pin "2") (pinfunction "FB_2") (pintype "input"))
    )
    (net (code "23") (name "Net-(U403-NR{slash}SS)") (class "Default")
      (node (ref "C424") (pin "2") (pinfunction "2_2") (pintype "passive"))
      (node (ref "U403") (pin "6") (pinfunction "NR/SS_6") (pintype "passive"))
    )
    (net (code "24") (name "Net-(U404-EN)") (class "Default")
      (node (ref "C418") (pin "2") (pinfunction "2_2") (pintype "passive"))
      (node (ref "L404") (pin "2") (pinfunction "2_2") (pintype "passive"))
      (node (ref "U404") (pin "5") (pinfunction "EN_5") (pintype "input"))
      (node (ref "U404") (pin "8") (pinfunction "IN_8") (pintype "power_in"))
    )
    (net (code "25") (name "Net-(U404-FB)") (class "Default")
      (node (ref "C429") (pin "1") (pinfunction "1_1") (pintype "passive"))
      (node (ref "R411") (pin "2") (pinfunction "2_2") (pintype "passive"))
      (node (ref "R412") (pin "1") (pinfunction "1_1") (pintype "passive"))
      (node (ref "U404") (pin "2") (pinfunction "FB_2") (pintype "input"))
    )
    (net (code "26") (name "Net-(U404-NR{slash}SS)") (class "Default")
      (node (ref "C423") (pin "2") (pinfunction "2_2") (pintype "passive"))
      (node (ref "U404") (pin "6") (pinfunction "NR/SS_6") (pintype "passive"))
    )
    (net (code "27") (name "Net-(U405-BYPASS)") (class "Default")
      (node (ref "C427") (pin "2") (pinfunction "2_2") (pintype "passive"))
      (node (ref "U405") (pin "4") (pinfunction "BYPASS_4") (pintype "passive"))
    )
    (net (code "28") (name "Net-(U405-ON{slash}~{OFF})") (class "Default")
      (node (ref "C419") (pin "2") (pinfunction "2_2") (pintype "passive"))
      (node (ref "L405") (pin "2") (pinfunction "2_2") (pintype "passive"))
      (node (ref "U405") (pin "1") (pinfunction "VIN_1") (pintype "power_in"))
      (node (ref "U405") (pin "3") (pinfunction "ON/~{OFF}_3") (pintype "input"))
    )
    (net (code "29") (name "Net-(U406-VIN)") (class "Default")
      (node (ref "C421") (pin "2") (pinfunction "2_2") (pintype "passive"))
      (node (ref "L407") (pin "2") (pinfunction "2_2") (pintype "passive"))
      (node (ref "U406") (pin "2") (pinfunction "VIN_2") (pintype "power_in"))
    )
    (net (code "30") (name "Net-(U407--IN)") (class "Default")
      (node (ref "C422") (pin "2") (pinfunction "2_2") (pintype "passive"))
      (node (ref "L408") (pin "2") (pinfunction "2_2") (pintype "passive"))
      (node (ref "U407") (pin "5") (pinfunction "-IN_5") (pintype "power_in"))
    )
    (net (code "31") (name "Net-(U408-EN)") (class "Default")
      (node (ref "C420") (pin "2") (pinfunction "2_2") (pintype "passive"))
      (node (ref "L406") (pin "2") (pinfunction "2_2") (pintype "passive"))
      (node (ref "U408") (pin "2") (pinfunction "IN_2") (pintype "power_in"))
      (node (ref "U408") (pin "3") (pinfunction "EN_3") (pintype "input"))
    )
    (net (code "32") (name "Net-(U408-NR)") (class "Default")
      (node (ref "C425") (pin "2") (pinfunction "2_2") (pintype "passive"))
      (node (ref "U408") (pin "4") (pinfunction "NR_4") (pintype "passive"))
    )
    (net (code "33") (name "VCCA+") (class "Default")
      (node (ref "C400") (pin "2") (pinfunction "2_2") (pintype "passive"))
      (node (ref "C429") (pin "2") (pinfunction "2_2") (pintype "passive"))
      (node (ref "C432") (pin "2") (pinfunction "2_2") (pintype "passive"))
      (node (ref "R412") (pin "2") (pinfunction "2_2") (pintype "passive"))
      (node (ref "TP408") (pin "1") (pinfunction "1_1") (pintype "passive"))
      (node (ref "U400") (pin "8") (pinfunction "V+_8") (pintype "power_in"))
      (node (ref "U404") (pin "1") (pinfunction "OUT_1") (pintype "power_in"))
    )
    (net (code "34") (name "VCCA-") (class "Default")
      (node (ref "C401") (pin "1") (pinfunction "1_1") (pintype "passive"))
      (node (ref "C430") (pin "2") (pinfunction "2_2") (pintype "passive"))
      (node (ref "C433") (pin "2") (pinfunction "2_2") (pintype "passive"))
      (node (ref "R413") (pin "2") (pinfunction "2_2") (pintype "passive"))
      (node (ref "TP409") (pin "1") (pinfunction "1_1") (pintype "passive"))
      (node (ref "U400") (pin "4") (pinfunction "V-_4") (pintype "power_in"))
      (node (ref "U403") (pin "1") (pinfunction "OUT_1") (pintype "power_in"))
    )
    (net (code "35") (name "VCOMP+") (class "Default")
      (node (ref "C416") (pin "2") (pinfunction "2_2") (pintype "passive"))
      (node (ref "R408") (pin "1") (pinfunction "1_1") (pintype "passive"))
      (node (ref "R409") (pin "2") (pinfunction "2_2") (pintype "passive"))
      (node (ref "TP404") (pin "1") (pinfunction "1_1") (pintype "passive"))
    )
    (net (code "36") (name "VCOMP-") (class "Default")
      (node (ref "C416") (pin "1") (pinfunction "1_1") (pintype "passive"))
      (node (ref "R410") (pin "1") (pinfunction "1_1") (pintype "passive"))
      (node (ref "TP405") (pin "1") (pinfunction "1_1") (pintype "passive"))
      (node (ref "U400") (pin "7") (pinfunction "2OUT_7") (pintype "output"))
    )
    (net (code "37") (name "VIN") (class "Default")
      (node (ref "C402") (pin "2") (pinfunction "2_2") (pintype "passive"))
      (node (ref "C403") (pin "2") (pinfunction "2_2") (pintype "passive"))
      (node (ref "C404") (pin "1") (pinfunction "1_1") (pintype "passive"))
      (node (ref "L400") (pin "2") (pinfunction "2_2") (pintype "passive"))
      (node (ref "L401") (pin "1") (pinfunction "1_1") (pintype "passive"))
      (node (ref "R400") (pin "2") (pinfunction "2_2") (pintype "passive"))
      (node (ref "TP401") (pin "1") (pinfunction "1_1") (pintype "passive"))
      (node (ref "U401") (pin "5") (pinfunction "INN5_5") (pintype "input"))
      (node (ref "U401") (pin "6") (pinfunction "INN6_6") (pintype "input"))
    )
    (net (code "38") (name "V_RAW") (class "Default")
      (node (ref "L400") (pin "1") (pinfunction "1_1") (pintype "passive"))
    )
    (net (code "39") (name "V_TH_D") (class "Default")
      (node (ref "C406") (pin "2") (pinfunction "2_2") (pintype "passive"))
      (node (ref "R401") (pin "2") (pinfunction "WIPER_2") (pintype "passive"))
      (node (ref "TP400") (pin "1") (pinfunction "1_1") (pintype "passive"))
    )
    (net (code "40") (name "unconnected-(U401-BSW-Pad7)") (class "Default")
      (node (ref "U401") (pin "7") (pinfunction "BSW_7") (pintype "output"))
    )
    (net (code "41") (name "unconnected-(U401-NC12-Pad12)") (class "Default")
      (node (ref "U401") (pin "12") (pinfunction "NC12_12") (pintype "passive"))
    )
    (net (code "42") (name "unconnected-(U401-NC20-Pad20)") (class "Default")
      (node (ref "U401") (pin "20") (pinfunction "NC20_20") (pintype "passive"))
    )
    (net (code "43") (name "unconnected-(U402-NC-Pad5)") (class "Default")
      (node (ref "U402") (pin "5") (pinfunction "NC_5") (pintype "passive"))
    )
    (net (code "44") (name "unconnected-(U403-DNC-Pad7)") (class "Default")
      (node (ref "U403") (pin "7") (pinfunction "DNC_7") (pintype "passive"))
    )
    (net (code "45") (name "unconnected-(U403-NC-Pad3)") (class "Default")
      (node (ref "U403") (pin "3") (pinfunction "NC_3") (pintype "passive"))
    )
    (net (code "46") (name "unconnected-(U404-DNC-Pad7)") (class "Default")
      (node (ref "U404") (pin "7") (pinfunction "DNC_7") (pintype "passive"))
    )
    (net (code "47") (name "unconnected-(U404-NC-Pad3)") (class "Default")
      (node (ref "U404") (pin "3") (pinfunction "NC_3") (pintype "passive"))
    )
  )
)
